# 1_P1.net
KiCad netlist of a schematic drawn in Altium Designer
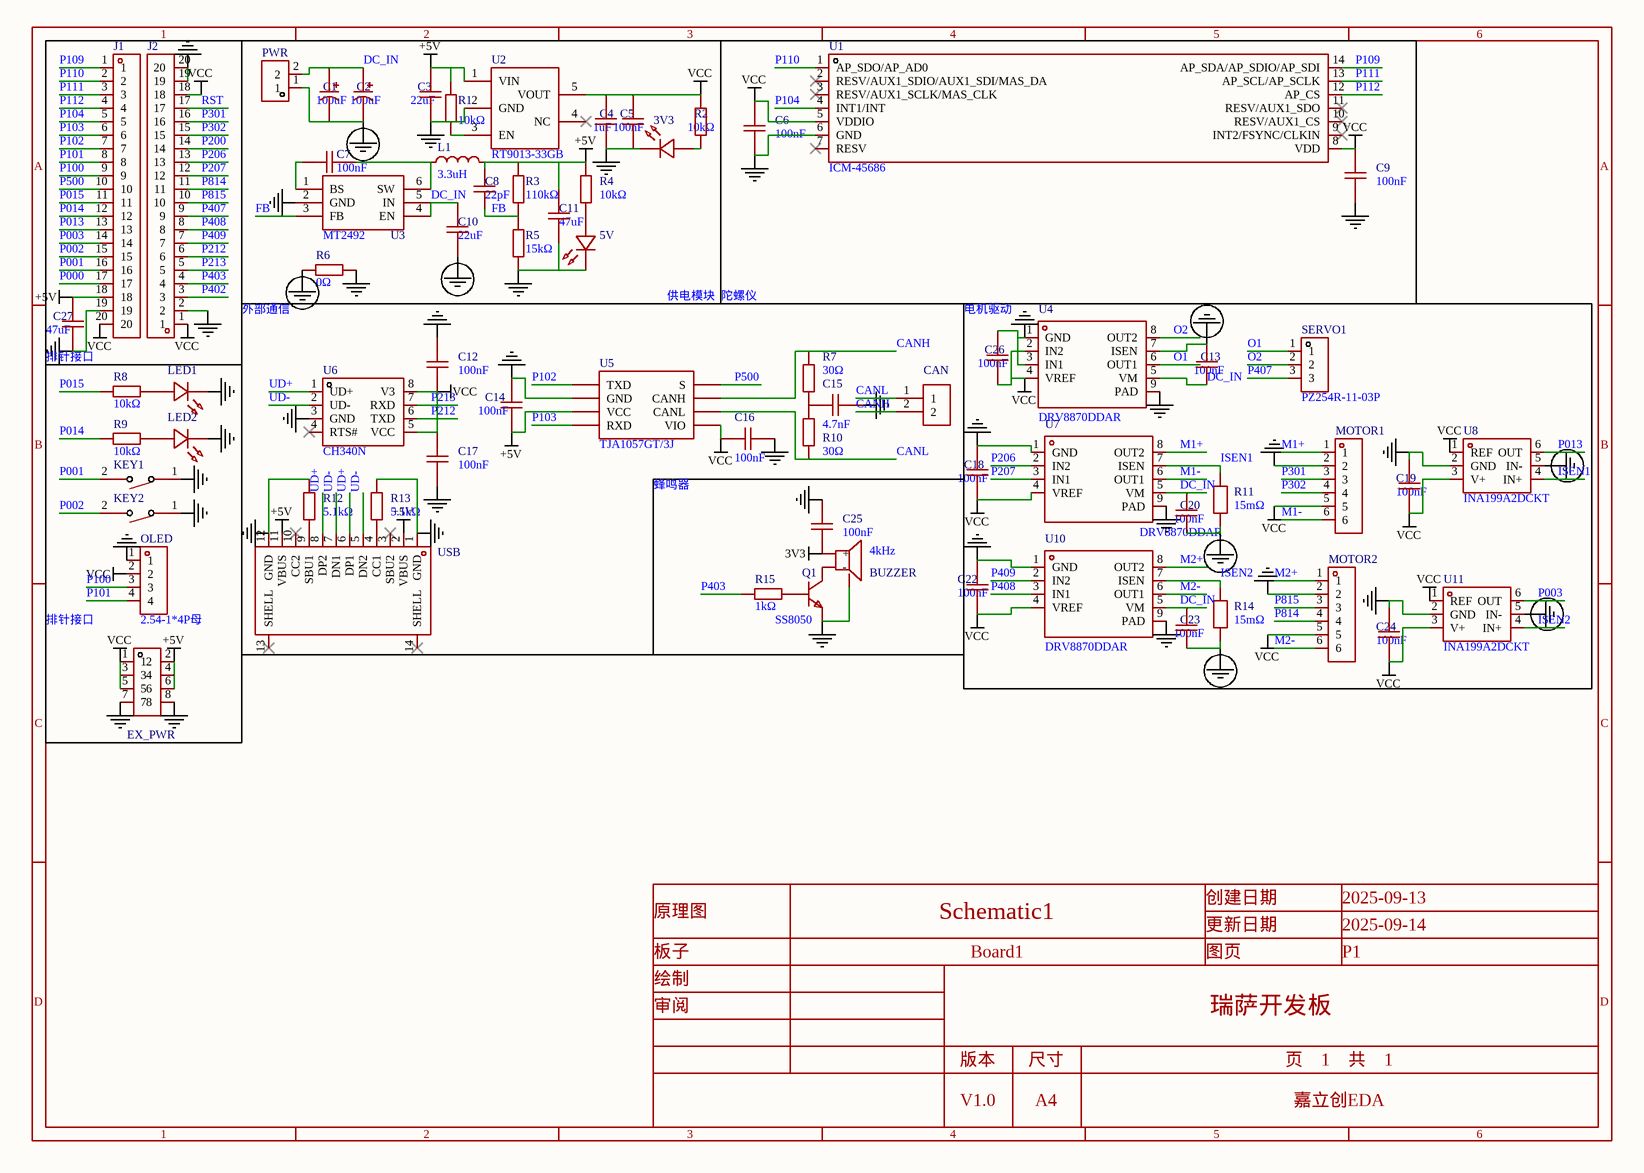
[diagram p0: 1_P1.schdoc]

(export (version "E")
  (design (tool "Eeschema 10.0.6"))
  (components
    (comp (ref "3V3")
      (value "XL-1608SURC-06")
      (footprint "LED0603-RD_RED")
      (fields (field (name "MANUFACTURER") "XINGLIGHT(成兴光)"))
      (libsource (lib "altium-import") (part "root_0_XL-1608SURC-06_"))
    )
    (comp (ref "5V")
      (value "XL-1608SURC-06")
      (footprint "LED0603-RD_RED")
      (fields (field (name "MANUFACTURER") "XINGLIGHT(成兴光)"))
      (libsource (lib "altium-import") (part "root_1_XL-1608SURC-06_"))
    )
    (comp (ref "BUZZER")
      (value "4kHz")
      (footprint "BUZ-SMD_L5.0-W5.5-P4.60")
      (fields (field (name "MANUFACTURER") "华能") (field (name "MANUFACTURER PART") "MLT-5020"))
      (libsource (lib "altium-import") (part "root_0_MLT-5020_"))
    )
    (comp (ref "C1")
      (value "100uF")
      (footprint "CAP-SMD_BD8.1-L8.3-W8.3-LS9.3-FD")
      (fields
        (field (name "MANUFACTURER") "HRK(鸿瑞凯电子)")
        (field (name "MANUFACTURER PART") "GVE1H107M0810CNVC")
        (field (name "TOLERANCE") "±20%")
      )
      (libsource (lib "altium-import") (part "root_3_GVE1H107M0810CNVC_"))
    )
    (comp (ref "C2")
      (value "100uF")
      (footprint "CAP-SMD_BD8.1-L8.3-W8.3-LS9.3-FD")
      (fields
        (field (name "MANUFACTURER") "HRK(鸿瑞凯电子)")
        (field (name "MANUFACTURER PART") "GVE1H107M0810CNVC")
        (field (name "TOLERANCE") "±20%")
      )
      (libsource (lib "altium-import") (part "root_3_GVE1H107M0810CNVC_"))
    )
    (comp (ref "C3")
      (value "22uF")
      (footprint "C0603")
      (fields
        (field (name "MANUFACTURER") "SAMSUNG(三星)")
        (field (name "MANUFACTURER PART") "CL10A226MO7JZNC")
        (field (name "TOLERANCE") "±20%")
      )
      (libsource (lib "altium-import") (part "root_1_CL10A226MO7JZNC_"))
    )
    (comp (ref "C4")
      (value "1uF")
      (footprint "C0603")
      (fields
        (field (name "MANUFACTURER") "SAMSUNG(三星)")
        (field (name "MANUFACTURER PART") "CL10A105KB8NNNC")
        (field (name "TOLERANCE") "±10%")
      )
      (libsource (lib "altium-import") (part "root_1_CL10A105KB8NNNC_"))
    )
    (comp (ref "C5")
      (value "100nF")
      (footprint "C0603")
      (fields
        (field (name "MANUFACTURER") "HRE(芯声)")
        (field (name "MANUFACTURER PART") "CGA0603X7R104K500JT")
        (field (name "TOLERANCE") "±10%")
      )
      (libsource (lib "altium-import") (part "root_1_CGA0603X7R104K500JT_"))
    )
    (comp (ref "C6")
      (value "100nF")
      (footprint "C0603")
      (fields
        (field (name "MANUFACTURER") "HRE(芯声)")
        (field (name "MANUFACTURER PART") "CGA0603X7R104K500JT")
        (field (name "TOLERANCE") "±10%")
      )
      (libsource (lib "altium-import") (part "root_1_CGA0603X7R104K500JT_"))
    )
    (comp (ref "C7")
      (value "100nF")
      (footprint "C0603")
      (fields
        (field (name "MANUFACTURER") "HRE(芯声)")
        (field (name "MANUFACTURER PART") "CGA0603X7R104K500JT")
        (field (name "TOLERANCE") "±10%")
      )
      (libsource (lib "altium-import") (part "root_2_CGA0603X7R104K500JT_"))
    )
    (comp (ref "C8")
      (value "22pF")
      (footprint "C0603")
      (fields
        (field (name "MANUFACTURER") "SAMSUNG(三星)")
        (field (name "MANUFACTURER PART") "CL10C220JB8NNNC")
        (field (name "TOLERANCE") "±5%")
      )
      (libsource (lib "altium-import") (part "root_1_CL10C220JB8NNNC_"))
    )
    (comp (ref "C9")
      (value "100nF")
      (footprint "C0603")
      (fields
        (field (name "MANUFACTURER") "HRE(芯声)")
        (field (name "MANUFACTURER PART") "CGA0603X7R104K500JT")
        (field (name "TOLERANCE") "±10%")
      )
      (libsource (lib "altium-import") (part "root_1_CGA0603X7R104K500JT_"))
    )
    (comp (ref "C10")
      (value "22uF")
      (footprint "C0805")
      (fields
        (field (name "MANUFACTURER") "SAMSUNG(三星)")
        (field (name "MANUFACTURER PART") "CL21A226MAQNNNE")
        (field (name "TOLERANCE") "±20%")
      )
      (libsource (lib "altium-import") (part "root_1_CL21A226MAQNNNE_"))
    )
    (comp (ref "C11")
      (value "47uF")
      (footprint "C0805")
      (fields
        (field (name "MANUFACTURER") "HRE(芯声)")
        (field (name "MANUFACTURER PART") "CGA0805X5R476M100MT")
        (field (name "TOLERANCE") "±20%")
      )
      (libsource (lib "altium-import") (part "root_1_CGA0805X5R476M100MT_"))
    )
    (comp (ref "C12")
      (value "100nF")
      (footprint "C0603")
      (fields
        (field (name "MANUFACTURER") "HRE(芯声)")
        (field (name "MANUFACTURER PART") "CGA0603X7R104K500JT")
        (field (name "TOLERANCE") "±10%")
      )
      (libsource (lib "altium-import") (part "root_1_CGA0603X7R104K500JT_"))
    )
    (comp (ref "C13")
      (value "100nF")
      (footprint "C0805")
      (fields
        (field (name "MANUFACTURER") "SAMSUNG(三星)")
        (field (name "MANUFACTURER PART") "CL21B104KBCNNNC")
        (field (name "TOLERANCE") "±10%")
      )
      (libsource (lib "altium-import") (part "root_1_CL21B104KBCNNNC_"))
    )
    (comp (ref "C14")
      (value "100nF")
      (footprint "C0805")
      (fields
        (field (name "MANUFACTURER") "YAGEO(国巨)")
        (field (name "MANUFACTURER PART") "CC0805KRX7R9BB104")
        (field (name "TOLERANCE") "±10%")
      )
      (libsource (lib "altium-import") (part "root_1_CC0805KRX7R9BB104_"))
    )
    (comp (ref "C15")
      (value "4.7nF")
      (footprint "C0603")
      (fields
        (field (name "MANUFACTURER") "HRE(芯声)")
        (field (name "MANUFACTURER PART") "CGA0603X7R472K500JT")
        (field (name "TOLERANCE") "±10%")
      )
      (libsource (lib "altium-import") (part "root_0_CGA0603X7R472K500JT_"))
    )
    (comp (ref "C16")
      (value "100nF")
      (footprint "C0603")
      (fields
        (field (name "MANUFACTURER") "HRE(芯声)")
        (field (name "MANUFACTURER PART") "CGA0603X7R104K500JT")
        (field (name "TOLERANCE") "±10%")
      )
      (libsource (lib "altium-import") (part "root_2_CGA0603X7R104K500JT_"))
    )
    (comp (ref "C17")
      (value "100nF")
      (footprint "C0603")
      (fields
        (field (name "MANUFACTURER") "HRE(芯声)")
        (field (name "MANUFACTURER PART") "CGA0603X7R104K500JT")
        (field (name "TOLERANCE") "±10%")
      )
      (libsource (lib "altium-import") (part "root_1_CGA0603X7R104K500JT_"))
    )
    (comp (ref "C18")
      (value "100nF")
      (footprint "C0603")
      (fields
        (field (name "MANUFACTURER") "HRE(芯声)")
        (field (name "MANUFACTURER PART") "CGA0603X7R104K500JT")
        (field (name "TOLERANCE") "±10%")
      )
      (libsource (lib "altium-import") (part "root_1_CGA0603X7R104K500JT_"))
    )
    (comp (ref "C19")
      (value "100nF")
      (footprint "C0603")
      (fields
        (field (name "MANUFACTURER") "HRE(芯声)")
        (field (name "MANUFACTURER PART") "CGA0603X7R104K500JT")
        (field (name "TOLERANCE") "±10%")
      )
      (libsource (lib "altium-import") (part "root_1_CGA0603X7R104K500JT_"))
    )
    (comp (ref "C20")
      (value "100nF")
      (footprint "C0805")
      (fields
        (field (name "MANUFACTURER") "SAMSUNG(三星)")
        (field (name "MANUFACTURER PART") "CL21B104KBCNNNC")
        (field (name "TOLERANCE") "±10%")
      )
      (libsource (lib "altium-import") (part "root_1_CL21B104KBCNNNC_"))
    )
    (comp (ref "C22")
      (value "100nF")
      (footprint "C0603")
      (fields
        (field (name "MANUFACTURER") "HRE(芯声)")
        (field (name "MANUFACTURER PART") "CGA0603X7R104K500JT")
        (field (name "TOLERANCE") "±10%")
      )
      (libsource (lib "altium-import") (part "root_1_CGA0603X7R104K500JT_"))
    )
    (comp (ref "C23")
      (value "100nF")
      (footprint "C0805")
      (fields
        (field (name "MANUFACTURER") "SAMSUNG(三星)")
        (field (name "MANUFACTURER PART") "CL21B104KBCNNNC")
        (field (name "TOLERANCE") "±10%")
      )
      (libsource (lib "altium-import") (part "root_1_CL21B104KBCNNNC_"))
    )
    (comp (ref "C24")
      (value "100nF")
      (footprint "C0603")
      (fields
        (field (name "MANUFACTURER") "HRE(芯声)")
        (field (name "MANUFACTURER PART") "CGA0603X7R104K500JT")
        (field (name "TOLERANCE") "±10%")
      )
      (libsource (lib "altium-import") (part "root_1_CGA0603X7R104K500JT_"))
    )
    (comp (ref "C25")
      (value "100nF")
      (footprint "C0603")
      (fields
        (field (name "MANUFACTURER") "HRE(芯声)")
        (field (name "MANUFACTURER PART") "CGA0603X7R104K500JT")
        (field (name "TOLERANCE") "±10%")
      )
      (libsource (lib "altium-import") (part "root_3_CGA0603X7R104K500JT_"))
    )
    (comp (ref "C26")
      (value "100nF")
      (footprint "C0603")
      (fields
        (field (name "MANUFACTURER") "HRE(芯声)")
        (field (name "MANUFACTURER PART") "CGA0603X7R104K500JT")
        (field (name "TOLERANCE") "±10%")
      )
      (libsource (lib "altium-import") (part "root_1_CGA0603X7R104K500JT_"))
    )
    (comp (ref "C27")
      (value "47uF")
      (footprint "C0805")
      (fields
        (field (name "MANUFACTURER") "HRE(芯声)")
        (field (name "MANUFACTURER PART") "CGA0805X5R476M100MT")
        (field (name "TOLERANCE") "±20%")
      )
      (libsource (lib "altium-import") (part "root_1_CGA0805X5R476M100MT_"))
    )
    (comp (ref "CAN")
      (value "WJ500V-5.08-2P")
      (footprint "CONN-TH_2P-P5.00_WJ500V-5.08-2P")
      (fields (field (name "MANUFACTURER") "KANGNEX(康奈克斯电气)"))
      (libsource (lib "altium-import") (part "root_3_WJ500V-5.08-2P_"))
    )
    (comp (ref "EX_PWR")
      (value "PZ254V-12-8P")
      (footprint "HDR-TH_8P-P2.54-V-M-R2-C4-S2.54")
      (fields (field (name "MANUFACTURER") "XFCN(兴飞)"))
      (libsource (lib "altium-import") (part "root_0_PZ254V-12-8P_"))
    )
    (comp (ref "J1")
      (value "ZX-PM2.54-1-20PY")
      (footprint "HDR-TH_20P-P2.54-V-F")
      (fields (field (name "MANUFACTURER") "Megastar(兆星)"))
      (libsource (lib "altium-import") (part "root_0_ZX-PM2.54-1-20PY_"))
    )
    (comp (ref "J2")
      (value "ZX-PM2.54-1-20PY")
      (footprint "HDR-TH_20P-P2.54-V-F")
      (fields (field (name "MANUFACTURER") "Megastar(兆星)"))
      (libsource (lib "altium-import") (part "root_2_ZX-PM2.54-1-20PY_"))
    )
    (comp (ref "KEY1")
      (value "TS-1088-AR02016")
      (footprint "SW-SMD_L3.9-W3.0-P4.45")
      (fields (field (name "MANUFACTURER") "XUNPU(讯普)"))
      (libsource (lib "altium-import") (part "root_2_TS-1088-AR02016_"))
    )
    (comp (ref "KEY2")
      (value "TS-1088-AR02016")
      (footprint "SW-SMD_L3.9-W3.0-P4.45")
      (fields (field (name "MANUFACTURER") "XUNPU(讯普)"))
      (libsource (lib "altium-import") (part "root_2_TS-1088-AR02016_"))
    )
    (comp (ref "L1")
      (value "3.3uH")
      (footprint "IND-SMD_L7.1-W6.6_MJC-0603T")
      (fields
        (field (name "MANUFACTURER") "DMBJ(振宝佳)")
        (field (name "MANUFACTURER PART") "CXP0630-3R3M-AG(3.3uh)")
        (field (name "TOLERANCE") "±20%")
      )
      (libsource (lib "altium-import") (part "root_0_CXP0630-3R3M-AG(3.3uh)_"))
    )
    (comp (ref "LED1")
      (value "XL-1608SURC-06")
      (footprint "LED0603-RD_RED")
      (fields (field (name "MANUFACTURER") "XINGLIGHT(成兴光)"))
      (libsource (lib "altium-import") (part "root_2_XL-1608SURC-06_"))
    )
    (comp (ref "LED2")
      (value "XL-1608SURC-06")
      (footprint "LED0603-RD_RED")
      (fields (field (name "MANUFACTURER") "XINGLIGHT(成兴光)"))
      (libsource (lib "altium-import") (part "root_2_XL-1608SURC-06_"))
    )
    (comp (ref "MOTOR1")
      (value "ZX-XH2.54-6PWZ")
      (footprint "CONN-TH_6P-P2.50_ZX-XH2.54-6PWZ")
      (fields (field (name "MANUFACTURER") "Megastar(兆星)"))
      (libsource (lib "altium-import") (part "root_0_ZX-XH2.54-6PWZ_"))
    )
    (comp (ref "MOTOR2")
      (value "ZX-XH2.54-6PWZ")
      (footprint "CONN-TH_6P-P2.50_ZX-XH2.54-6PWZ")
      (fields (field (name "MANUFACTURER") "Megastar(兆星)"))
      (libsource (lib "altium-import") (part "root_0_ZX-XH2.54-6PWZ_"))
    )
    (comp (ref "OLED")
      (value "2.54-1*4P母")
      (footprint "HDR-TH_4P-P2.54-V-F")
      (fields (field (name "MANUFACTURER") "BOOMELE(博穆精密)"))
      (libsource (lib "altium-import") (part "root_0_2.54-1*4P母_"))
    )
    (comp (ref "PWR")
      (value "PZ254V-11-02P")
      (footprint "HDR-TH_2P-P2.54-V-M")
      (fields (field (name "MANUFACTURER") "XFCN(兴飞)"))
      (libsource (lib "altium-import") (part "root_2_PZ254V-11-02P_"))
    )
    (comp (ref "Q1")
      (value "SS8050")
      (footprint "SOT-23-3_L2.9-W1.3-P1.90-LS2.4-BR")
      (fields (field (name "MANUFACTURER") "宏嘉诚"))
      (libsource (lib "altium-import") (part "root_0_SS8050_C7420370_"))
    )
    (comp (ref "R1")
      (value "10kΩ")
      (footprint "R0603")
      (fields
        (field (name "MANUFACTURER") "UNI-ROYAL(厚声)")
        (field (name "MANUFACTURER PART") "0603WAF1002T5E")
        (field (name "TOLERANCE") "±1%")
      )
      (libsource (lib "altium-import") (part "root_3_0603WAF1002T5E_"))
    )
    (comp (ref "R2")
      (value "10kΩ")
      (footprint "R0603")
      (fields
        (field (name "MANUFACTURER") "UNI-ROYAL(厚声)")
        (field (name "MANUFACTURER PART") "0603WAF1002T5E")
        (field (name "TOLERANCE") "±1%")
      )
      (libsource (lib "altium-import") (part "root_1_0603WAF1002T5E_"))
    )
    (comp (ref "R3")
      (value "110kΩ")
      (footprint "R0402")
      (fields
        (field (name "MANUFACTURER") "YAGEO(国巨)")
        (field (name "MANUFACTURER PART") "RC0402FR-07110KL")
        (field (name "TOLERANCE") "±1%")
      )
      (libsource (lib "altium-import") (part "root_1_RC0402FR-07110KL_"))
    )
    (comp (ref "R4")
      (value "10kΩ")
      (footprint "R0603")
      (fields
        (field (name "MANUFACTURER") "UNI-ROYAL(厚声)")
        (field (name "MANUFACTURER PART") "0603WAF1002T5E")
        (field (name "TOLERANCE") "±1%")
      )
      (libsource (lib "altium-import") (part "root_1_0603WAF1002T5E_"))
    )
    (comp (ref "R5")
      (value "15kΩ")
      (footprint "R0402")
      (fields
        (field (name "MANUFACTURER") "UNI-ROYAL(厚声)")
        (field (name "MANUFACTURER PART") "0402WGF1502TCE")
        (field (name "TOLERANCE") "±1%")
      )
      (libsource (lib "altium-import") (part "root_1_0402WGF1502TCE_"))
    )
    (comp (ref "R6")
      (value "0Ω")
      (footprint "R0603")
      (fields
        (field (name "MANUFACTURER") "UNI-ROYAL(厚声)")
        (field (name "MANUFACTURER PART") "0603WAF0000T5E")
        (field (name "TOLERANCE") "±1%")
      )
      (libsource (lib "altium-import") (part "root_0_0603WAF0000T5E_"))
    )
    (comp (ref "R7")
      (value "30Ω")
      (footprint "R0603")
      (fields
        (field (name "MANUFACTURER") "UNI-ROYAL(厚声)")
        (field (name "MANUFACTURER PART") "0603WAF300JT5E")
        (field (name "TOLERANCE") "±1%")
      )
      (libsource (lib "altium-import") (part "root_1_0603WAF300JT5E_"))
    )
    (comp (ref "R8")
      (value "10kΩ")
      (footprint "R0603")
      (fields
        (field (name "MANUFACTURER") "UNI-ROYAL(厚声)")
        (field (name "MANUFACTURER PART") "0603WAF1002T5E")
        (field (name "TOLERANCE") "±1%")
      )
      (libsource (lib "altium-import") (part "root_2_0603WAF1002T5E_"))
    )
    (comp (ref "R9")
      (value "10kΩ")
      (footprint "R0603")
      (fields
        (field (name "MANUFACTURER") "UNI-ROYAL(厚声)")
        (field (name "MANUFACTURER PART") "0603WAF1002T5E")
        (field (name "TOLERANCE") "±1%")
      )
      (libsource (lib "altium-import") (part "root_2_0603WAF1002T5E_"))
    )
    (comp (ref "R10")
      (value "30Ω")
      (footprint "R0603")
      (fields
        (field (name "MANUFACTURER") "UNI-ROYAL(厚声)")
        (field (name "MANUFACTURER PART") "0603WAF300JT5E")
        (field (name "TOLERANCE") "±1%")
      )
      (libsource (lib "altium-import") (part "root_1_0603WAF300JT5E_"))
    )
    (comp (ref "R11")
      (value "15mΩ")
      (footprint "RES-SMD_L6.4-W3.2-R2512")
      (fields
        (field (name "MANUFACTURER") "JIERR(捷而瑞)")
        (field (name "MANUFACTURER PART") "JER2512F3R015")
        (field (name "TOLERANCE") "±1%")
      )
      (libsource (lib "altium-import") (part "root_1_JER2512F3R015_"))
    )
    (comp (ref "R12")
      (value "5.1kΩ")
      (footprint "R0402")
      (fields
        (field (name "MANUFACTURER") "UNI-ROYAL(厚声)")
        (field (name "MANUFACTURER PART") "0402WGF5101TCE")
        (field (name "TOLERANCE") "±1%")
      )
      (libsource (lib "altium-import") (part "root_3_0402WGF5101TCE_"))
    )
    (comp (ref "R13")
      (value "5.1kΩ")
      (footprint "R0402")
      (fields
        (field (name "MANUFACTURER") "UNI-ROYAL(厚声)")
        (field (name "MANUFACTURER PART") "0402WGF5101TCE")
        (field (name "TOLERANCE") "±1%")
      )
      (libsource (lib "altium-import") (part "root_3_0402WGF5101TCE_"))
    )
    (comp (ref "R14")
      (value "15mΩ")
      (footprint "RES-SMD_L6.4-W3.2-R2512")
      (fields
        (field (name "MANUFACTURER") "JIERR(捷而瑞)")
        (field (name "MANUFACTURER PART") "JER2512F3R015")
        (field (name "TOLERANCE") "±1%")
      )
      (libsource (lib "altium-import") (part "root_1_JER2512F3R015_"))
    )
    (comp (ref "R15")
      (value "1kΩ")
      (footprint "R0603")
      (fields
        (field (name "MANUFACTURER") "UNI-ROYAL(厚声)")
        (field (name "MANUFACTURER PART") "0603WAF1001T5E")
        (field (name "TOLERANCE") "±1%")
      )
      (libsource (lib "altium-import") (part "root_0_0603WAF1001T5E_"))
    )
    (comp (ref "SERVO1")
      (value "PZ254R-11-03P")
      (footprint "HDR-TH_3P-P2.54-H-M-W10.4")
      (fields (field (name "MANUFACTURER") "XFCN(兴飞)"))
      (libsource (lib "altium-import") (part "root_0_PZ254R-11-03P_"))
    )
    (comp (ref "U1")
      (value "ICM-45686")
      (footprint "LGA-14_L3.0-W2.5-P0.50-TL")
      (fields (field (name "MANUFACTURER") "TDK InvenSense(应美盛)"))
      (libsource (lib "altium-import") (part "root_0_ICM-45686_"))
    )
    (comp (ref "U2")
      (value "RT9013-33GB")
      (footprint "SOT-23-5_L3.0-W1.7-P0.95-LS2.8-BL")
      (fields (field (name "MANUFACTURER") "RICHTEK(立锜)"))
      (libsource (lib "altium-import") (part "root_0_RT9013-33GB_"))
    )
    (comp (ref "U3")
      (value "MT2492")
      (footprint "SOT-23-6_L2.9-W1.6-P0.95-LS2.8-BL_3")
      (fields (field (name "MANUFACTURER") "西安航天民芯"))
      (libsource (lib "altium-import") (part "root_0_MT2492_"))
    )
    (comp (ref "U4")
      (value "DRV8870DDAR")
      (footprint "HSOP-8_L5.0-W4.0-P1.27-LS6.2-BL-EP")
      (fields (field (name "MANUFACTURER") "TI(德州仪器)"))
      (libsource (lib "altium-import") (part "root_0_DRV8870DDAR_"))
    )
    (comp (ref "U5")
      (value "TJA1057GT/3J")
      (footprint "SOIC-8_L4.9-W3.9-P1.27-LS6.0-BL")
      (fields (field (name "MANUFACTURER") "NXP(恩智浦)"))
      (libsource (lib "altium-import") (part "root_0_TJA1057GT/3J_"))
    )
    (comp (ref "U6")
      (value "CH340N")
      (footprint "SOP-8_L4.9-W3.9-P1.27-LS6.0-BL")
      (fields (field (name "MANUFACTURER") "WCH(南京沁恒)"))
      (libsource (lib "altium-import") (part "root_0_CH340N_"))
    )
    (comp (ref "U7")
      (value "DRV8870DDAR")
      (footprint "HSOP-8_L5.0-W4.0-P1.27-LS6.2-BL-EP")
      (fields (field (name "MANUFACTURER") "TI(德州仪器)"))
      (libsource (lib "altium-import") (part "root_0_DRV8870DDAR_"))
    )
    (comp (ref "U8")
      (value "INA199A2DCKT")
      (footprint "SC-70-6_L2.0-W1.3-P0.65-LS2.1-BR")
      (fields (field (name "MANUFACTURER") "TI(德州仪器)"))
      (libsource (lib "altium-import") (part "root_0_INA199A2DCKT_"))
    )
    (comp (ref "U10")
      (value "DRV8870DDAR")
      (footprint "HSOP-8_L5.0-W4.0-P1.27-LS6.2-BL-EP")
      (fields (field (name "MANUFACTURER") "TI(德州仪器)"))
      (libsource (lib "altium-import") (part "root_0_DRV8870DDAR_"))
    )
    (comp (ref "U11")
      (value "INA199A2DCKT")
      (footprint "SC-70-6_L2.0-W1.3-P0.65-LS2.1-BR")
      (fields (field (name "MANUFACTURER") "TI(德州仪器)"))
      (libsource (lib "altium-import") (part "root_0_INA199A2DCKT_"))
    )
    (comp (ref "USB")
      (value "TYPE-C 16PIN 2MD(073)")
      (footprint "USB-C-SMD_TYPE-C-6PIN-2MD-073")
      (fields (field (name "MANUFACTURER") "SHOU HAN(首韩)"))
      (libsource (lib "altium-import") (part "root_3_TYPE-C 16PIN 2MD(073)_"))
    )
  )
  (nets
    (net (code "1") (name "+5V") (class "Default")
      (node (ref "C11") (pin "2") (pinfunction "2_2") (pintype "passive"))
      (node (ref "C14") (pin "1") (pinfunction "1_1") (pintype "passive"))
      (node (ref "C27") (pin "2") (pinfunction "2_2") (pintype "passive"))
      (node (ref "C3") (pin "1") (pinfunction "1_1") (pintype "passive"))
      (node (ref "C8") (pin "2") (pinfunction "2_2") (pintype "passive"))
      (node (ref "EX_PWR") (pin "2") (pinfunction "2_2") (pintype "passive"))
      (node (ref "EX_PWR") (pin "4") (pinfunction "4_4") (pintype "passive"))
      (node (ref "EX_PWR") (pin "6") (pinfunction "6_6") (pintype "passive"))
      (node (ref "J1") (pin "18") (pinfunction "18_18") (pintype "passive"))
      (node (ref "L1") (pin "2") (pinfunction "2_2") (pintype "passive"))
      (node (ref "R1") (pin "1") (pinfunction "1_1") (pintype "passive"))
      (node (ref "R3") (pin "2") (pinfunction "2_2") (pintype "passive"))
      (node (ref "R4") (pin "2") (pinfunction "2_2") (pintype "passive"))
      (node (ref "U2") (pin "1") (pinfunction "VIN_1") (pintype "passive"))
      (node (ref "U5") (pin "3") (pinfunction "VCC_3") (pintype "passive"))
      (node (ref "USB") (pin "11") (pinfunction "VBUS_11") (pintype "passive"))
      (node (ref "USB") (pin "2") (pinfunction "VBUS_2") (pintype "passive"))
    )
    (net (code "2") (name "/CANH") (class "Default")
      (node (ref "CAN") (pin "2") (pinfunction "2_2") (pintype "passive"))
      (node (ref "R7") (pin "2") (pinfunction "2_2") (pintype "passive"))
      (node (ref "U5") (pin "7") (pinfunction "CANH_7") (pintype "passive"))
    )
    (net (code "3") (name "/CANL") (class "Default")
      (node (ref "CAN") (pin "1") (pinfunction "1_1") (pintype "passive"))
      (node (ref "R10") (pin "1") (pinfunction "1_1") (pintype "passive"))
      (node (ref "U5") (pin "6") (pinfunction "CANL_6") (pintype "passive"))
    )
    (net (code "4") (name "/DC_IN") (class "Default")
      (node (ref "C1") (pin "1") (pinfunction "1_1") (pintype "passive"))
      (node (ref "C10") (pin "2") (pinfunction "2_2") (pintype "passive"))
      (node (ref "C13") (pin "1") (pinfunction "1_1") (pintype "passive"))
      (node (ref "C2") (pin "1") (pinfunction "1_1") (pintype "passive"))
      (node (ref "C20") (pin "2") (pinfunction "2_2") (pintype "passive"))
      (node (ref "C23") (pin "2") (pinfunction "2_2") (pintype "passive"))
      (node (ref "PWR") (pin "2") (pinfunction "2_2") (pintype "passive"))
      (node (ref "U10") (pin "5") (pinfunction "VM_5") (pintype "passive"))
      (node (ref "U3") (pin "4") (pinfunction "EN_4") (pintype "passive"))
      (node (ref "U3") (pin "5") (pinfunction "IN_5") (pintype "passive"))
      (node (ref "U4") (pin "5") (pinfunction "VM_5") (pintype "passive"))
      (node (ref "U7") (pin "5") (pinfunction "VM_5") (pintype "passive"))
    )
    (net (code "5") (name "/FB") (class "Default")
      (node (ref "C8") (pin "1") (pinfunction "1_1") (pintype "passive"))
      (node (ref "R3") (pin "1") (pinfunction "1_1") (pintype "passive"))
      (node (ref "R5") (pin "2") (pinfunction "2_2") (pintype "passive"))
      (node (ref "U3") (pin "3") (pinfunction "FB_3") (pintype "passive"))
    )
    (net (code "6") (name "/ISEN1") (class "Default")
      (node (ref "R11") (pin "2") (pinfunction "2_2") (pintype "passive"))
      (node (ref "U7") (pin "7") (pinfunction "ISEN_7") (pintype "passive"))
      (node (ref "U8") (pin "4") (pinfunction "IN+_4") (pintype "passive"))
    )
    (net (code "7") (name "/ISEN2") (class "Default")
      (node (ref "R14") (pin "2") (pinfunction "2_2") (pintype "passive"))
      (node (ref "U10") (pin "7") (pinfunction "ISEN_7") (pintype "passive"))
      (node (ref "U11") (pin "4") (pinfunction "IN+_4") (pintype "passive"))
    )
    (net (code "8") (name "/M1+") (class "Default")
      (node (ref "MOTOR1") (pin "1") (pinfunction "1_1") (pintype "passive"))
      (node (ref "U7") (pin "8") (pinfunction "OUT2_8") (pintype "passive"))
    )
    (net (code "9") (name "/M1-") (class "Default")
      (node (ref "MOTOR1") (pin "6") (pinfunction "6_6") (pintype "passive"))
      (node (ref "U7") (pin "6") (pinfunction "OUT1_6") (pintype "passive"))
    )
    (net (code "10") (name "/M2+") (class "Default")
      (node (ref "MOTOR2") (pin "1") (pinfunction "1_1") (pintype "passive"))
      (node (ref "U10") (pin "8") (pinfunction "OUT2_8") (pintype "passive"))
    )
    (net (code "11") (name "/M2-") (class "Default")
      (node (ref "MOTOR2") (pin "6") (pinfunction "6_6") (pintype "passive"))
      (node (ref "U10") (pin "6") (pinfunction "OUT1_6") (pintype "passive"))
    )
    (net (code "12") (name "/O1") (class "Default")
      (node (ref "SERVO1") (pin "1") (pinfunction "1_1") (pintype "passive"))
      (node (ref "U4") (pin "6") (pinfunction "OUT1_6") (pintype "passive"))
    )
    (net (code "13") (name "/O2") (class "Default")
      (node (ref "SERVO1") (pin "2") (pinfunction "2_2") (pintype "passive"))
      (node (ref "U4") (pin "8") (pinfunction "OUT2_8") (pintype "passive"))
    )
    (net (code "14") (name "/P000") (class "Default")
      (node (ref "J1") (pin "17") (pinfunction "17_17") (pintype "passive"))
    )
    (net (code "15") (name "/P001") (class "Default")
      (node (ref "J1") (pin "16") (pinfunction "16_16") (pintype "passive"))
      (node (ref "KEY1") (pin "2") (pinfunction "2_2") (pintype "passive"))
    )
    (net (code "16") (name "/P002") (class "Default")
      (node (ref "J1") (pin "15") (pinfunction "15_15") (pintype "passive"))
      (node (ref "KEY2") (pin "2") (pinfunction "2_2") (pintype "passive"))
    )
    (net (code "17") (name "/P003") (class "Default")
      (node (ref "J1") (pin "14") (pinfunction "14_14") (pintype "passive"))
      (node (ref "U11") (pin "6") (pinfunction "OUT_6") (pintype "passive"))
    )
    (net (code "18") (name "/P013") (class "Default")
      (node (ref "J1") (pin "13") (pinfunction "13_13") (pintype "passive"))
      (node (ref "U8") (pin "6") (pinfunction "OUT_6") (pintype "passive"))
    )
    (net (code "19") (name "/P014") (class "Default")
      (node (ref "J1") (pin "12") (pinfunction "12_12") (pintype "passive"))
      (node (ref "R9") (pin "2") (pinfunction "2_2") (pintype "passive"))
    )
    (net (code "20") (name "/P015") (class "Default")
      (node (ref "J1") (pin "11") (pinfunction "11_11") (pintype "passive"))
      (node (ref "R8") (pin "2") (pinfunction "2_2") (pintype "passive"))
    )
    (net (code "21") (name "/P100") (class "Default")
      (node (ref "J1") (pin "9") (pinfunction "9_9") (pintype "passive"))
      (node (ref "OLED") (pin "3") (pinfunction "3_3") (pintype "passive"))
    )
    (net (code "22") (name "/P101") (class "Default")
      (node (ref "J1") (pin "8") (pinfunction "8_8") (pintype "passive"))
      (node (ref "OLED") (pin "4") (pinfunction "4_4") (pintype "passive"))
    )
    (net (code "23") (name "/P102") (class "Default")
      (node (ref "J1") (pin "7") (pinfunction "7_7") (pintype "passive"))
      (node (ref "U5") (pin "1") (pinfunction "TXD_1") (pintype "passive"))
    )
    (net (code "24") (name "/P103") (class "Default")
      (node (ref "J1") (pin "6") (pinfunction "6_6") (pintype "passive"))
      (node (ref "U5") (pin "4") (pinfunction "RXD_4") (pintype "passive"))
    )
    (net (code "25") (name "/P104") (class "Default")
      (node (ref "J1") (pin "5") (pinfunction "5_5") (pintype "passive"))
      (node (ref "U1") (pin "4") (pinfunction "INT1/INT_4") (pintype "passive"))
    )
    (net (code "26") (name "/P109") (class "Default")
      (node (ref "J1") (pin "1") (pinfunction "1_1") (pintype "passive"))
      (node (ref "U1") (pin "14") (pinfunction "AP_SDA/AP_SDIO/AP_SDI_14") (pintype "passive"))
    )
    (net (code "27") (name "/P110") (class "Default")
      (node (ref "J1") (pin "2") (pinfunction "2_2") (pintype "passive"))
      (node (ref "U1") (pin "1") (pinfunction "AP_SDO/AP_AD0_1") (pintype "passive"))
    )
    (net (code "28") (name "/P111") (class "Default")
      (node (ref "J1") (pin "3") (pinfunction "3_3") (pintype "passive"))
      (node (ref "U1") (pin "13") (pinfunction "AP_SCL/AP_SCLK_13") (pintype "passive"))
    )
    (net (code "29") (name "/P112") (class "Default")
      (node (ref "J1") (pin "4") (pinfunction "4_4") (pintype "passive"))
      (node (ref "U1") (pin "12") (pinfunction "AP_CS_12") (pintype "passive"))
    )
    (net (code "30") (name "/P200") (class "Default")
      (node (ref "J2") (pin "14") (pinfunction "14_14") (pintype "passive"))
    )
    (net (code "31") (name "/P206") (class "Default")
      (node (ref "J2") (pin "13") (pinfunction "13_13") (pintype "passive"))
      (node (ref "U7") (pin "2") (pinfunction "IN2_2") (pintype "passive"))
    )
    (net (code "32") (name "/P207") (class "Default")
      (node (ref "J2") (pin "12") (pinfunction "12_12") (pintype "passive"))
      (node (ref "U7") (pin "3") (pinfunction "IN1_3") (pintype "passive"))
    )
    (net (code "33") (name "/P212") (class "Default")
      (node (ref "J2") (pin "6") (pinfunction "6_6") (pintype "passive"))
      (node (ref "U6") (pin "6") (pinfunction "TXD_6") (pintype "passive"))
    )
    (net (code "34") (name "/P213") (class "Default")
      (node (ref "J2") (pin "5") (pinfunction "5_5") (pintype "passive"))
      (node (ref "U6") (pin "7") (pinfunction "RXD_7") (pintype "passive"))
    )
    (net (code "35") (name "/P301") (class "Default")
      (node (ref "J2") (pin "16") (pinfunction "16_16") (pintype "passive"))
      (node (ref "MOTOR1") (pin "3") (pinfunction "3_3") (pintype "passive"))
    )
    (net (code "36") (name "/P302") (class "Default")
      (node (ref "J2") (pin "15") (pinfunction "15_15") (pintype "passive"))
      (node (ref "MOTOR1") (pin "4") (pinfunction "4_4") (pintype "passive"))
    )
    (net (code "37") (name "/P402") (class "Default")
      (node (ref "J2") (pin "3") (pinfunction "3_3") (pintype "passive"))
    )
    (net (code "38") (name "/P403") (class "Default")
      (node (ref "J2") (pin "4") (pinfunction "4_4") (pintype "passive"))
      (node (ref "R15") (pin "1") (pinfunction "1_1") (pintype "passive"))
    )
    (net (code "39") (name "/P407") (class "Default")
      (node (ref "J2") (pin "9") (pinfunction "9_9") (pintype "passive"))
      (node (ref "SERVO1") (pin "3") (pinfunction "3_3") (pintype "passive"))
    )
    (net (code "40") (name "/P408") (class "Default")
      (node (ref "J2") (pin "8") (pinfunction "8_8") (pintype "passive"))
      (node (ref "U10") (pin "3") (pinfunction "IN1_3") (pintype "passive"))
    )
    (net (code "41") (name "/P409") (class "Default")
      (node (ref "J2") (pin "7") (pinfunction "7_7") (pintype "passive"))
      (node (ref "U10") (pin "2") (pinfunction "IN2_2") (pintype "passive"))
    )
    (net (code "42") (name "/P500") (class "Default")
      (node (ref "J1") (pin "10") (pinfunction "10_10") (pintype "passive"))
      (node (ref "U5") (pin "8") (pinfunction "S_8") (pintype "passive"))
    )
    (net (code "43") (name "/P814") (class "Default")
      (node (ref "J2") (pin "11") (pinfunction "11_11") (pintype "passive"))
      (node (ref "MOTOR2") (pin "4") (pinfunction "4_4") (pintype "passive"))
    )
    (net (code "44") (name "/P815") (class "Default")
      (node (ref "J2") (pin "10") (pinfunction "10_10") (pintype "passive"))
      (node (ref "MOTOR2") (pin "3") (pinfunction "3_3") (pintype "passive"))
    )
    (net (code "45") (name "/RST") (class "Default")
      (node (ref "J2") (pin "17") (pinfunction "17_17") (pintype "passive"))
    )
    (net (code "46") (name "/UD+") (class "Default")
      (node (ref "U6") (pin "1") (pinfunction "UD+_1") (pintype "passive"))
      (node (ref "USB") (pin "6") (pinfunction "DP1_6") (pintype "passive"))
      (node (ref "USB") (pin "8") (pinfunction "DP2_8") (pintype "passive"))
    )
    (net (code "47") (name "/UD-") (class "Default")
      (node (ref "U6") (pin "2") (pinfunction "UD-_2") (pintype "passive"))
      (node (ref "USB") (pin "5") (pinfunction "DN2_5") (pintype "passive"))
      (node (ref "USB") (pin "7") (pinfunction "DN1_7") (pintype "passive"))
    )
    (net (code "48") (name "3V3") (class "Default")
      (node (ref "BUZZER") (pin "1") (pinfunction "+_1") (pintype "passive"))
      (node (ref "C25") (pin "2") (pinfunction "2_2") (pintype "passive"))
    )
    (net (code "49") (name "GND") (class "Default")
      (node (ref "3V3") (pin "1") (pinfunction "K_1") (pintype "passive"))
      (node (ref "5V") (pin "1") (pinfunction "K_1") (pintype "passive"))
      (node (ref "BUZZER") (pin "3") (pinfunction "NC_3") (pintype "passive"))
      (node (ref "C11") (pin "1") (pinfunction "1_1") (pintype "passive"))
      (node (ref "C12") (pin "2") (pinfunction "2_2") (pintype "passive"))
      (node (ref "C14") (pin "2") (pinfunction "2_2") (pintype "passive"))
      (node (ref "C15") (pin "2") (pinfunction "2_2") (pintype "passive"))
      (node (ref "C16") (pin "1") (pinfunction "1_1") (pintype "passive"))
      (node (ref "C17") (pin "1") (pinfunction "1_1") (pintype "passive"))
      (node (ref "C18") (pin "2") (pinfunction "2_2") (pintype "passive"))
      (node (ref "C19") (pin "2") (pinfunction "2_2") (pintype "passive"))
      (node (ref "C22") (pin "2") (pinfunction "2_2") (pintype "passive"))
      (node (ref "C24") (pin "2") (pinfunction "2_2") (pintype "passive"))
      (node (ref "C25") (pin "1") (pinfunction "1_1") (pintype "passive"))
      (node (ref "C26") (pin "2") (pinfunction "2_2") (pintype "passive"))
      (node (ref "C27") (pin "1") (pinfunction "1_1") (pintype "passive"))
      (node (ref "C3") (pin "2") (pinfunction "2_2") (pintype "passive"))
      (node (ref "C4") (pin "1") (pinfunction "1_1") (pintype "passive"))
      (node (ref "C5") (pin "1") (pinfunction "1_1") (pintype "passive"))
      (node (ref "C6") (pin "1") (pinfunction "1_1") (pintype "passive"))
      (node (ref "C9") (pin "1") (pinfunction "1_1") (pintype "passive"))
      (node (ref "EX_PWR") (pin "7") (pinfunction "7_7") (pintype "passive"))
      (node (ref "EX_PWR") (pin "8") (pinfunction "8_8") (pintype "passive"))
      (node (ref "J1") (pin "19") (pinfunction "19_19") (pintype "passive"))
      (node (ref "J2") (pin "19") (pinfunction "19_19") (pintype "passive"))
      (node (ref "J2") (pin "2") (pinfunction "2_2") (pintype "passive"))
      (node (ref "J2") (pin "20") (pinfunction "20_20") (pintype "passive"))
      (node (ref "KEY1") (pin "1") (pinfunction "1_1") (pintype "passive"))
      (node (ref "KEY2") (pin "1") (pinfunction "1_1") (pintype "passive"))
      (node (ref "LED1") (pin "1") (pinfunction "K_1") (pintype "passive"))
      (node (ref "LED2") (pin "1") (pinfunction "K_1") (pintype "passive"))
      (node (ref "MOTOR1") (pin "2") (pinfunction "2_2") (pintype "passive"))
      (node (ref "MOTOR2") (pin "2") (pinfunction "2_2") (pintype "passive"))
      (node (ref "OLED") (pin "1") (pinfunction "1_1") (pintype "passive"))
      (node (ref "Q1") (pin "2") (pinfunction "E_2") (pintype "passive"))
      (node (ref "R12") (pin "1") (pinfunction "1_1") (pintype "passive"))
      (node (ref "R13") (pin "1") (pinfunction "1_1") (pintype "passive"))
      (node (ref "R5") (pin "1") (pinfunction "1_1") (pintype "passive"))
      (node (ref "R6") (pin "2") (pinfunction "2_2") (pintype "passive"))
      (node (ref "U1") (pin "6") (pinfunction "GND_6") (pintype "passive"))
      (node (ref "U10") (pin "1") (pinfunction "GND_1") (pintype "passive"))
      (node (ref "U10") (pin "9") (pinfunction "PAD_9") (pintype "passive"))
      (node (ref "U11") (pin "2") (pinfunction "GND_2") (pintype "passive"))
      (node (ref "U2") (pin "2") (pinfunction "GND_2") (pintype "passive"))
      (node (ref "U3") (pin "2") (pinfunction "GND_2") (pintype "passive"))
      (node (ref "U4") (pin "1") (pinfunction "GND_1") (pintype "passive"))
      (node (ref "U4") (pin "3") (pinfunction "IN1_3") (pintype "passive"))
      (node (ref "U4") (pin "9") (pinfunction "PAD_9") (pintype "passive"))
      (node (ref "U5") (pin "2") (pinfunction "GND_2") (pintype "passive"))
      (node (ref "U6") (pin "3") (pinfunction "GND_3") (pintype "passive"))
      (node (ref "U7") (pin "1") (pinfunction "GND_1") (pintype "passive"))
      (node (ref "U7") (pin "9") (pinfunction "PAD_9") (pintype "passive"))
      (node (ref "U8") (pin "2") (pinfunction "GND_2") (pintype "passive"))
      (node (ref "USB") (pin "1") (pinfunction "GND_1") (pintype "passive"))
      (node (ref "USB") (pin "12") (pinfunction "GND_12") (pintype "passive"))
    )
    (net (code "50") (name "Net-(3V3-A)") (class "Default")
      (node (ref "3V3") (pin "2") (pinfunction "A_2") (pintype "passive"))
      (node (ref "R2") (pin "1") (pinfunction "1_1") (pintype "passive"))
    )
    (net (code "51") (name "Net-(5V-A)") (class "Default")
      (node (ref "5V") (pin "2") (pinfunction "A_2") (pintype "passive"))
      (node (ref "R4") (pin "1") (pinfunction "1_1") (pintype "passive"))
    )
    (net (code "52") (name "Net-(BUZZER--)") (class "Default")
      (node (ref "BUZZER") (pin "2") (pinfunction "-_2") (pintype "passive"))
      (node (ref "Q1") (pin "3") (pinfunction "C_3") (pintype "passive"))
    )
    (net (code "53") (name "Net-(C15-Pad1)") (class "Default")
      (node (ref "C15") (pin "1") (pinfunction "1_1") (pintype "passive"))
      (node (ref "R10") (pin "2") (pinfunction "2_2") (pintype "passive"))
      (node (ref "R7") (pin "1") (pinfunction "1_1") (pintype "passive"))
    )
    (net (code "54") (name "Net-(LED1-A)") (class "Default")
      (node (ref "LED1") (pin "2") (pinfunction "A_2") (pintype "passive"))
      (node (ref "R8") (pin "1") (pinfunction "1_1") (pintype "passive"))
    )
    (net (code "55") (name "Net-(LED2-A)") (class "Default")
      (node (ref "LED2") (pin "2") (pinfunction "A_2") (pintype "passive"))
      (node (ref "R9") (pin "1") (pinfunction "1_1") (pintype "passive"))
    )
    (net (code "56") (name "Net-(Q1-B)") (class "Default")
      (node (ref "Q1") (pin "1") (pinfunction "B_1") (pintype "passive"))
      (node (ref "R15") (pin "2") (pinfunction "2_2") (pintype "passive"))
    )
    (net (code "57") (name "Net-(U2-EN)") (class "Default")
      (node (ref "R1") (pin "2") (pinfunction "2_2") (pintype "passive"))
      (node (ref "U2") (pin "3") (pinfunction "EN_3") (pintype "passive"))
    )
    (net (code "58") (name "Net-(U3-BS)") (class "Default")
      (node (ref "C7") (pin "2") (pinfunction "2_2") (pintype "passive"))
      (node (ref "U3") (pin "1") (pinfunction "BS_1") (pintype "passive"))
    )
    (net (code "59") (name "Net-(U3-SW)") (class "Default")
      (node (ref "C7") (pin "1") (pinfunction "1_1") (pintype "passive"))
      (node (ref "L1") (pin "1") (pinfunction "1_1") (pintype "passive"))
      (node (ref "U3") (pin "6") (pinfunction "SW_6") (pintype "passive"))
    )
    (net (code "60") (name "Net-(USB-CC1)") (class "Default")
      (node (ref "R13") (pin "2") (pinfunction "2_2") (pintype "passive"))
      (node (ref "USB") (pin "4") (pinfunction "CC1_4") (pintype "passive"))
    )
    (net (code "61") (name "Net-(USB-SBU1)") (class "Default")
      (node (ref "R12") (pin "2") (pinfunction "2_2") (pintype "passive"))
      (node (ref "USB") (pin "9") (pinfunction "SBU1_9") (pintype "passive"))
    )
    (net (code "62") (name "PGND") (class "Default")
      (node (ref "C1") (pin "2") (pinfunction "2_2") (pintype "passive"))
      (node (ref "C10") (pin "1") (pinfunction "1_1") (pintype "passive"))
      (node (ref "C13") (pin "2") (pinfunction "2_2") (pintype "passive"))
      (node (ref "C2") (pin "2") (pinfunction "2_2") (pintype "passive"))
      (node (ref "C20") (pin "1") (pinfunction "1_1") (pintype "passive"))
      (node (ref "C23") (pin "1") (pinfunction "1_1") (pintype "passive"))
      (node (ref "PWR") (pin "1") (pinfunction "1_1") (pintype "passive"))
      (node (ref "R11") (pin "1") (pinfunction "1_1") (pintype "passive"))
      (node (ref "R14") (pin "1") (pinfunction "1_1") (pintype "passive"))
      (node (ref "R6") (pin "1") (pinfunction "1_1") (pintype "passive"))
      (node (ref "U11") (pin "5") (pinfunction "IN-_5") (pintype "passive"))
      (node (ref "U4") (pin "7") (pinfunction "ISEN_7") (pintype "passive"))
      (node (ref "U8") (pin "5") (pinfunction "IN-_5") (pintype "passive"))
    )
    (net (code "63") (name "VCC") (class "Default")
      (node (ref "C12") (pin "1") (pinfunction "1_1") (pintype "passive"))
      (node (ref "C16") (pin "2") (pinfunction "2_2") (pintype "passive"))
      (node (ref "C17") (pin "2") (pinfunction "2_2") (pintype "passive"))
      (node (ref "C18") (pin "1") (pinfunction "1_1") (pintype "passive"))
      (node (ref "C19") (pin "1") (pinfunction "1_1") (pintype "passive"))
      (node (ref "C22") (pin "1") (pinfunction "1_1") (pintype "passive"))
      (node (ref "C24") (pin "1") (pinfunction "1_1") (pintype "passive"))
      (node (ref "C26") (pin "1") (pinfunction "1_1") (pintype "passive"))
      (node (ref "C4") (pin "2") (pinfunction "2_2") (pintype "passive"))
      (node (ref "C5") (pin "2") (pinfunction "2_2") (pintype "passive"))
      (node (ref "C6") (pin "2") (pinfunction "2_2") (pintype "passive"))
      (node (ref "C9") (pin "2") (pinfunction "2_2") (pintype "passive"))
      (node (ref "EX_PWR") (pin "1") (pinfunction "1_1") (pintype "passive"))
      (node (ref "EX_PWR") (pin "3") (pinfunction "3_3") (pintype "passive"))
      (node (ref "EX_PWR") (pin "5") (pinfunction "5_5") (pintype "passive"))
      (node (ref "J1") (pin "20") (pinfunction "20_20") (pintype "passive"))
      (node (ref "J2") (pin "1") (pinfunction "1_1") (pintype "passive"))
      (node (ref "J2") (pin "18") (pinfunction "18_18") (pintype "passive"))
      (node (ref "MOTOR1") (pin "5") (pinfunction "5_5") (pintype "passive"))
      (node (ref "MOTOR2") (pin "5") (pinfunction "5_5") (pintype "passive"))
      (node (ref "OLED") (pin "2") (pinfunction "2_2") (pintype "passive"))
      (node (ref "R2") (pin "2") (pinfunction "2_2") (pintype "passive"))
      (node (ref "U1") (pin "5") (pinfunction "VDDIO_5") (pintype "passive"))
      (node (ref "U1") (pin "8") (pinfunction "VDD_8") (pintype "passive"))
      (node (ref "U10") (pin "4") (pinfunction "VREF_4") (pintype "passive"))
      (node (ref "U11") (pin "1") (pinfunction "REF_1") (pintype "passive"))
      (node (ref "U11") (pin "3") (pinfunction "V+_3") (pintype "passive"))
      (node (ref "U2") (pin "5") (pinfunction "VOUT_5") (pintype "passive"))
      (node (ref "U4") (pin "2") (pinfunction "IN2_2") (pintype "passive"))
      (node (ref "U4") (pin "4") (pinfunction "VREF_4") (pintype "passive"))
      (node (ref "U5") (pin "5") (pinfunction "VIO_5") (pintype "passive"))
      (node (ref "U6") (pin "5") (pinfunction "VCC_5") (pintype "passive"))
      (node (ref "U6") (pin "8") (pinfunction "V3_8") (pintype "passive"))
      (node (ref "U7") (pin "4") (pinfunction "VREF_4") (pintype "passive"))
      (node (ref "U8") (pin "1") (pinfunction "REF_1") (pintype "passive"))
      (node (ref "U8") (pin "3") (pinfunction "V+_3") (pintype "passive"))
    )
    (net (code "64") (name "unconnected-(U1-INT2{slash}FSYNC{slash}CLKIN-Pad9)") (class "Default")
      (node (ref "U1") (pin "9") (pinfunction "INT2/FSYNC/CLKIN_9") (pintype "passive+no_connect"))
    )
    (net (code "65") (name "unconnected-(U1-RESV-Pad7)") (class "Default")
      (node (ref "U1") (pin "7") (pinfunction "RESV_7") (pintype "passive+no_connect"))
    )
    (net (code "66") (name "unconnected-(U1-RESV{slash}AUX1_CS-Pad10)") (class "Default")
      (node (ref "U1") (pin "10") (pinfunction "RESV/AUX1_CS_10") (pintype "passive+no_connect"))
    )
    (net (code "67") (name "unconnected-(U1-RESV{slash}AUX1_SCLK{slash}MAS_CLK-Pad3)") (class "Default")
      (node (ref "U1") (pin "3") (pinfunction "RESV/AUX1_SCLK/MAS_CLK_3") (pintype "passive+no_connect"))
    )
    (net (code "68") (name "unconnected-(U1-RESV{slash}AUX1_SDIO{slash}AUX1_SDI{slash}MAS_DA-Pad2)") (class "Default")
      (node (ref "U1") (pin "2") (pinfunction "RESV/AUX1_SDIO/AUX1_SDI/MAS_DA_2") (pintype "passive+no_connect"))
    )
    (net (code "69") (name "unconnected-(U1-RESV{slash}AUX1_SDO-Pad11)") (class "Default")
      (node (ref "U1") (pin "11") (pinfunction "RESV/AUX1_SDO_11") (pintype "passive+no_connect"))
    )
    (net (code "70") (name "unconnected-(U2-NC-Pad4)") (class "Default")
      (node (ref "U2") (pin "4") (pinfunction "NC_4") (pintype "passive+no_connect"))
    )
    (net (code "71") (name "unconnected-(U6-RTS#-Pad4)") (class "Default")
      (node (ref "U6") (pin "4") (pinfunction "RTS#_4") (pintype "passive+no_connect"))
    )
    (net (code "72") (name "unconnected-(USB-CC2-Pad10)") (class "Default")
      (node (ref "USB") (pin "10") (pinfunction "CC2_10") (pintype "passive+no_connect"))
    )
    (net (code "73") (name "unconnected-(USB-SBU2-Pad3)") (class "Default")
      (node (ref "USB") (pin "3") (pinfunction "SBU2_3") (pintype "passive+no_connect"))
    )
    (net (code "74") (name "unconnected-(USB-SHELL-Pad13)") (class "Default")
      (node (ref "USB") (pin "13") (pinfunction "SHELL_13") (pintype "passive+no_connect"))
    )
    (net (code "75") (name "unconnected-(USB-SHELL-Pad14)") (class "Default")
      (node (ref "USB") (pin "14") (pinfunction "SHELL_14") (pintype "passive+no_connect"))
    )
  )
)
